# TC_SMPS.net
KiCad netlist of a schematic drawn in Altium Designer
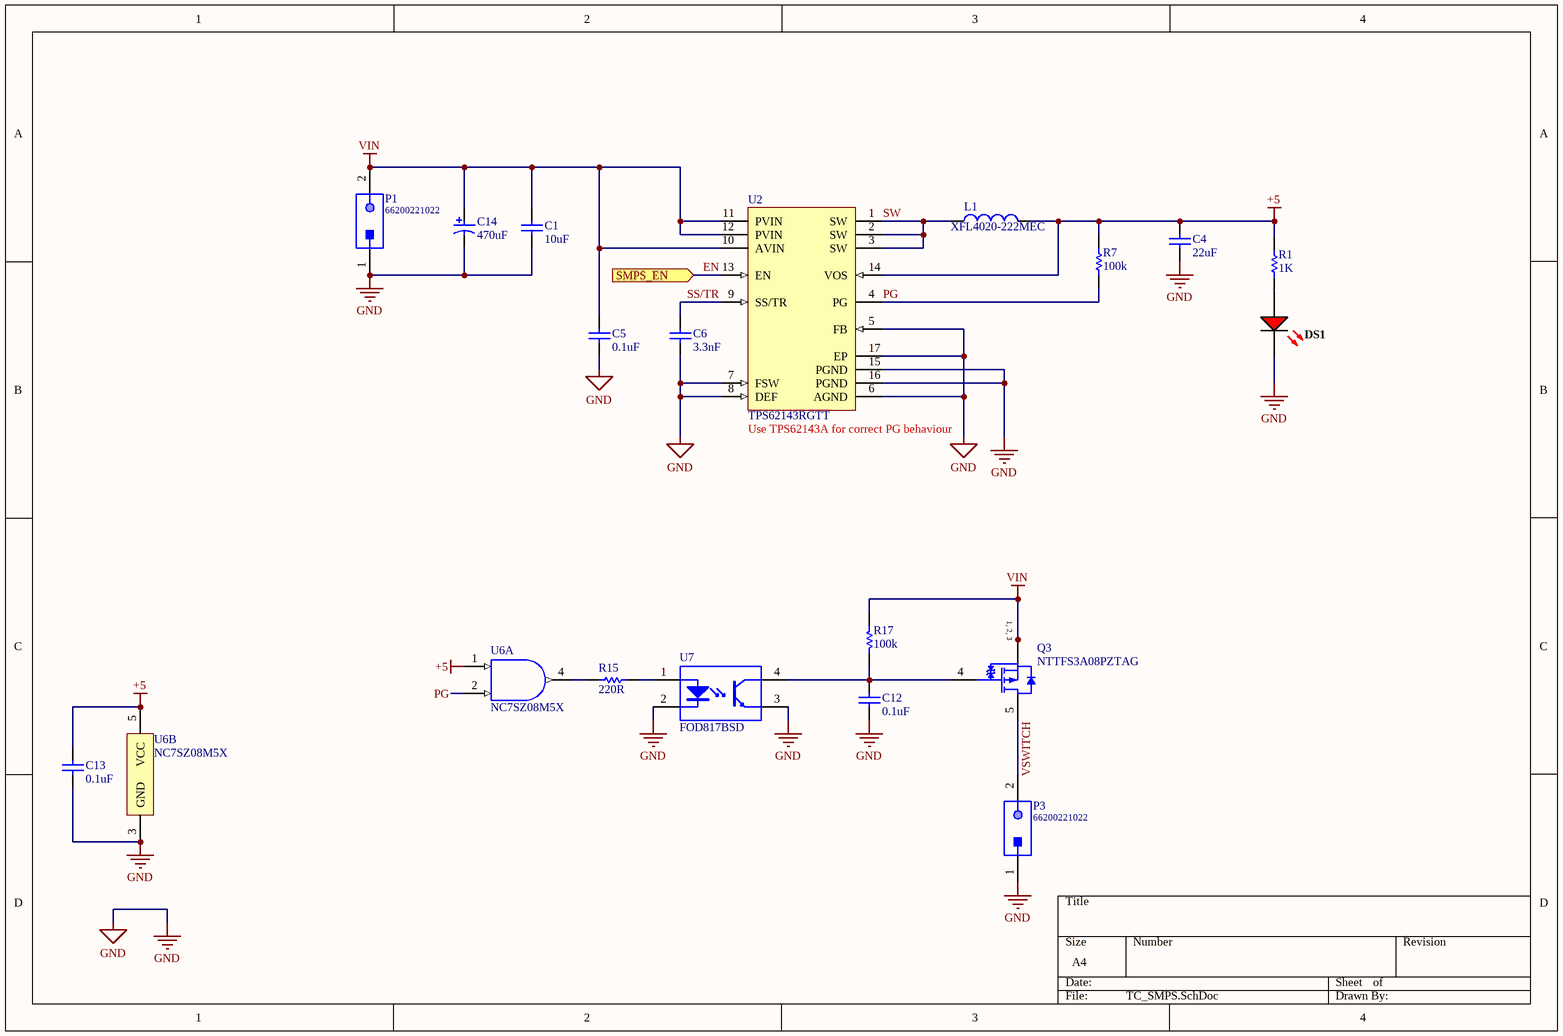
[diagram p0: TC_SMPS.SchDoc]

(export (version "E")
  (design (tool "Eeschema 10.0.6"))
  (components
    (comp (ref "C1")
      (value "10uF")
      (footprint "CAPC1210(3225)210_M")
      (description "CAP 10uF 35V ±20% 1210 (3225 Metric) Thickness 2.1mm SMD")
      (fields (field (name "TOLERANCE") "Â±20%"))
      (libsource (lib "Altium Content Vault") (part "CAP"))
    )
    (comp (ref "C4")
      (value "22uF")
      (footprint "CAPC2013X95X45ML15T25")
      (fields (field (name "MANUFACTURER") "Murata") (field (name "PART NUMBER") "GRM219R61A226MEA0D"))
      (libsource (lib "Altium Content Vault") (part "CAP"))
    )
    (comp (ref "C5")
      (value "0.1uF")
      (footprint "CAPC1608X87X35NL15T15")
      (fields (field (name "PART NUMBER") "C0603X104K5RACTU") (field (name "MANUFACTURER") "Kemet"))
      (libsource (lib "Altium Content Vault") (part "CAP"))
    )
    (comp (ref "C6")
      (value "3.3nF")
      (footprint "CAPC1608X87X35NL15T15")
      (fields (field (name "PART NUMBER") "C0603C332K5RAC7867") (field (name "MANUFACTURER") "Kemet"))
      (libsource (lib "Altium Content Vault") (part "CAP"))
    )
    (comp (ref "C12")
      (value "0.1uF")
      (footprint "CAPC1608X87X35NL15T15")
      (fields (field (name "PART NUMBER") "C0603X104K5RACTU") (field (name "MANUFACTURER") "Kemet"))
      (libsource (lib "Altium Content Vault") (part "CAP"))
    )
    (comp (ref "C13")
      (value "0.1uF")
      (footprint "CAPC1608X87X35NL15T15")
      (fields (field (name "PART NUMBER") "C0603X104K5RACTU") (field (name "MANUFACTURER") "Kemet"))
      (libsource (lib "Altium Content Vault") (part "CAP"))
    )
    (comp (ref "C14")
      (value "470uF")
      (footprint "PNSC-FK-V-F_V")
      (fields (field (name "MANUFACTURER") "Panasonic"))
      (libsource (lib "Altium Content Vault") (part "CAP-P-2"))
    )
    (comp (ref "DS1")
      (value "APG1608SURKC/T")
      (footprint "KING-LED0603-25-RED_V")
      (fields (field (name "MANUFACTURER") "Kingbright"))
      (libsource (lib "Altium Content Vault") (part "KING-LED_RED_A1K2-2"))
    )
    (comp (ref "L1")
      (value "XFL4020-222MEC")
      (footprint "COIL-IND-2_V")
      (fields (field (name "MANUFACTURER") "Coilcraft") (field (name "TOLERANCE") "20%"))
      (libsource (lib "Altium Content Vault") (part "IND-2"))
    )
    (comp (ref "P1")
      (value "66200221022")
      (footprint "66200221022")
      (description "THT Male Header WR-MPC3, with Snap-in Plastic Pegs, Right Angled, Dual Row, pitch 3 mm, 2 pins")
      (fields (field (name "MANUFACTURER") "Wurth Elektronik") (field (name "PUBLISHER") "WurthElektronik"))
      (libsource (lib "Altium Content Vault") (part "WE-CN-2P-M-R2"))
    )
    (comp (ref "P3")
      (value "66200221022")
      (footprint "66200221022")
      (description "THT Male Header WR-MPC3, with Snap-in Plastic Pegs, Right Angled, Dual Row, pitch 3 mm, 2 pins")
      (fields (field (name "MANUFACTURER") "Wurth Elektronik") (field (name "PUBLISHER") "WurthElektronik"))
      (libsource (lib "") (part "WE-CN-2P-M-R2_1"))
    )
    (comp (ref "Q3")
      (value "NTTFS3A08PZTAG")
      (footprint "ONSC-WDFN-8-511AB_V")
      (description "Power MOSFET, -20 V, -15 A, Single P-Channel, 8-Pin WDFN, Pb-Free, Tape and Reel")
      (fields (field (name "MANUFACTURER") "On Semiconductor"))
      (libsource (lib "Altium Content Vault") (part "ONSC-NTTFS3A08PZ-WDFN-8-511AB"))
    )
    (comp (ref "R1")
      (value "1K")
      (footprint "RESC1608X55X30LL15T15")
      (fields (field (name "PART NUMBER") "ERJ-3EKF1001V") (field (name "MANUFACTURER") "Panasonic"))
      (libsource (lib "Altium Content Vault") (part "RES"))
    )
    (comp (ref "R7")
      (value "100k")
      (footprint "RESC1608X55X25ML10T15")
      (description "Chip Resistor, 100 KOhm, +/- 1%, 0.1 W, -55 to 155 degC, 0603 (1608 Metric), RoHS, Tape and Reel")
      (fields (field (name "MANUFACTURER") "Yageo") (field (name "TOLERANCE") "1%"))
      (libsource (lib "Altium Content Vault") (part "RES-2"))
    )
    (comp (ref "R15")
      (value "220R")
      (footprint "RESC1609X50X30LL10T20")
      (fields (field (name "PART NUMBER") "CRCW0603220RFKEA") (field (name "MANUFACTURER") "Vishay Dale"))
      (libsource (lib "Altium Content Vault") (part "RES"))
    )
    (comp (ref "R17")
      (value "100k")
      (footprint "RESC1608X55X25ML10T15")
      (description "Chip Resistor, 100 KOhm, +/- 1%, 0.1 W, -55 to 155 degC, 0603 (1608 Metric), RoHS, Tape and Reel")
      (fields (field (name "MANUFACTURER") "Yageo") (field (name "TOLERANCE") "1%"))
      (libsource (lib "Altium Content Vault") (part "RES-2"))
    )
    (comp (ref "U2")
      (value "TPS62143RGTT")
      (footprint "RGT0016C_V")
      (fields (field (name "MANUFACTURER") "Texas Instruments"))
      (libsource (lib "Altium Content Vault") (part "TI-TPS62143RGT16-1700X1700TP"))
    )
    (comp (ref "U6")
      (value "NC7SZ08M5X")
      (footprint "FAIR-SOT23-5_V")
      (description "TinyLogic(R) UHS 2-Input AND Gate, 1.65 to 5.5 V, -40 to 85 degC, 5-Pin SOT23, RoHS, Tape and Reel")
      (fields (field (name "MANUFACTURER") "FairchildSemiconductor"))
      (libsource (lib "Altium Content Vault") (part "AND-1-2IN-5"))
    )
    (comp (ref "U7")
      (value "FOD817BSD")
      (footprint "FAIR-MDIP-4_V")
      (fields (field (name "MANUFACTURER") "Fairchild Semiconductor"))
      (libsource (lib "Altium Content Vault") (part "OPTO-AKEC-4"))
    )
  )
  (nets
    (net (code "1") (name "+5") (class "Default")
      (node (ref "C13") (pin "1") (pinfunction "1_1") (pintype "passive"))
      (node (ref "C4") (pin "2") (pinfunction "2_2") (pintype "passive"))
      (node (ref "L1") (pin "2") (pinfunction "2_2") (pintype "passive"))
      (node (ref "R1") (pin "2") (pinfunction "2_2") (pintype "passive"))
      (node (ref "R7") (pin "2") (pinfunction "2_2") (pintype "passive"))
      (node (ref "U2") (pin "14") (pinfunction "VOS_14") (pintype "input"))
      (node (ref "U6") (pin "1") (pinfunction "A_1") (pintype "input"))
      (node (ref "U6") (pin "5") (pinfunction "VCC_5") (pintype "power_in"))
    )
    (net (code "2") (name "/EN") (class "Default")
      (node (ref "U2") (pin "13") (pinfunction "EN_13") (pintype "input"))
    )
    (net (code "3") (name "/PG") (class "Default")
      (node (ref "R7") (pin "1") (pinfunction "1_1") (pintype "passive"))
      (node (ref "U2") (pin "4") (pinfunction "PG_4") (pintype "tri_state"))
      (node (ref "U6") (pin "2") (pinfunction "B_2") (pintype "input"))
    )
    (net (code "4") (name "/SS{slash}TR") (class "Default")
      (node (ref "C6") (pin "2") (pinfunction "2_2") (pintype "passive"))
      (node (ref "U2") (pin "9") (pinfunction "SS/TR_9") (pintype "input"))
    )
    (net (code "5") (name "/SW") (class "Default")
      (node (ref "L1") (pin "1") (pinfunction "1_1") (pintype "passive"))
      (node (ref "U2") (pin "1") (pinfunction "SW_1") (pintype "power_in"))
      (node (ref "U2") (pin "2") (pinfunction "SW_2") (pintype "power_in"))
      (node (ref "U2") (pin "3") (pinfunction "SW_3") (pintype "power_in"))
    )
    (net (code "6") (name "/VSWITCH") (class "Default")
      (node (ref "P3") (pin "2") (pinfunction "2_2") (pintype "passive"))
      (node (ref "Q3") (pin "5") (pinfunction "D_5") (pintype "passive"))
    )
    (net (code "7") (name "GND") (class "Default")
      (node (ref "C1") (pin "1") (pinfunction "1_1") (pintype "passive"))
      (node (ref "C12") (pin "2") (pinfunction "2_2") (pintype "passive"))
      (node (ref "C13") (pin "2") (pinfunction "2_2") (pintype "passive"))
      (node (ref "C14") (pin "2") (pinfunction "2_2") (pintype "passive"))
      (node (ref "C4") (pin "1") (pinfunction "1_1") (pintype "passive"))
      (node (ref "C5") (pin "2") (pinfunction "2_2") (pintype "passive"))
      (node (ref "C6") (pin "1") (pinfunction "1_1") (pintype "passive"))
      (node (ref "DS1") (pin "2") (pinfunction "K_2") (pintype "passive"))
      (node (ref "P1") (pin "1") (pinfunction "1_1") (pintype "passive"))
      (node (ref "P3") (pin "1") (pinfunction "1_1") (pintype "passive"))
      (node (ref "U2") (pin "15") (pinfunction "PGND_15") (pintype "power_in"))
      (node (ref "U2") (pin "16") (pinfunction "PGND_16") (pintype "power_in"))
      (node (ref "U2") (pin "17") (pinfunction "EP_17") (pintype "power_in"))
      (node (ref "U2") (pin "5") (pinfunction "FB_5") (pintype "input"))
      (node (ref "U2") (pin "6") (pinfunction "AGND_6") (pintype "power_in"))
      (node (ref "U2") (pin "7") (pinfunction "FSW_7") (pintype "input"))
      (node (ref "U2") (pin "8") (pinfunction "DEF_8") (pintype "input"))
      (node (ref "U6") (pin "3") (pinfunction "GND_3") (pintype "power_in"))
      (node (ref "U7") (pin "2") (pinfunction "CATHODE_2") (pintype "passive"))
      (node (ref "U7") (pin "3") (pinfunction "EMITTER_3") (pintype "passive"))
    )
    (net (code "8") (name "Net-(DS1-A)") (class "Default")
      (node (ref "DS1") (pin "1") (pinfunction "A_1") (pintype "passive"))
      (node (ref "R1") (pin "1") (pinfunction "1_1") (pintype "passive"))
    )
    (net (code "9") (name "Net-(Q3-G)") (class "Default")
      (node (ref "C12") (pin "1") (pinfunction "1_1") (pintype "passive"))
      (node (ref "Q3") (pin "4") (pinfunction "G_4") (pintype "passive"))
      (node (ref "R17") (pin "1") (pinfunction "1_1") (pintype "passive"))
      (node (ref "U7") (pin "4") (pinfunction "COLLECTOR_4") (pintype "passive"))
    )
    (net (code "10") (name "Net-(U6A-Y)") (class "Default")
      (node (ref "R15") (pin "1") (pinfunction "1_1") (pintype "passive"))
      (node (ref "U6") (pin "4") (pinfunction "Y_4") (pintype "output"))
    )
    (net (code "11") (name "Net-(U7-ANODE)") (class "Default")
      (node (ref "R15") (pin "2") (pinfunction "2_2") (pintype "passive"))
      (node (ref "U7") (pin "1") (pinfunction "ANODE_1") (pintype "passive"))
    )
    (net (code "12") (name "VIN") (class "Default")
      (node (ref "C1") (pin "2") (pinfunction "2_2") (pintype "passive"))
      (node (ref "C14") (pin "1") (pinfunction "1_1") (pintype "passive"))
      (node (ref "C5") (pin "1") (pinfunction "1_1") (pintype "passive"))
      (node (ref "P1") (pin "2") (pinfunction "2_2") (pintype "passive"))
      (node (ref "Q3") (pin "1") (pinfunction "S_1") (pintype "passive"))
      (node (ref "Q3") (pin "2") (pinfunction "S_2") (pintype "passive"))
      (node (ref "Q3") (pin "3") (pinfunction "S_3") (pintype "passive"))
      (node (ref "R17") (pin "2") (pinfunction "2_2") (pintype "passive"))
      (node (ref "U2") (pin "10") (pinfunction "AVIN_10") (pintype "power_in"))
      (node (ref "U2") (pin "11") (pinfunction "PVIN_11") (pintype "power_in"))
      (node (ref "U2") (pin "12") (pinfunction "PVIN_12") (pintype "power_in"))
    )
  )
)
